# KeepUntil-v2_0.net
KiCad netlist of a schematic drawn in EAGLE
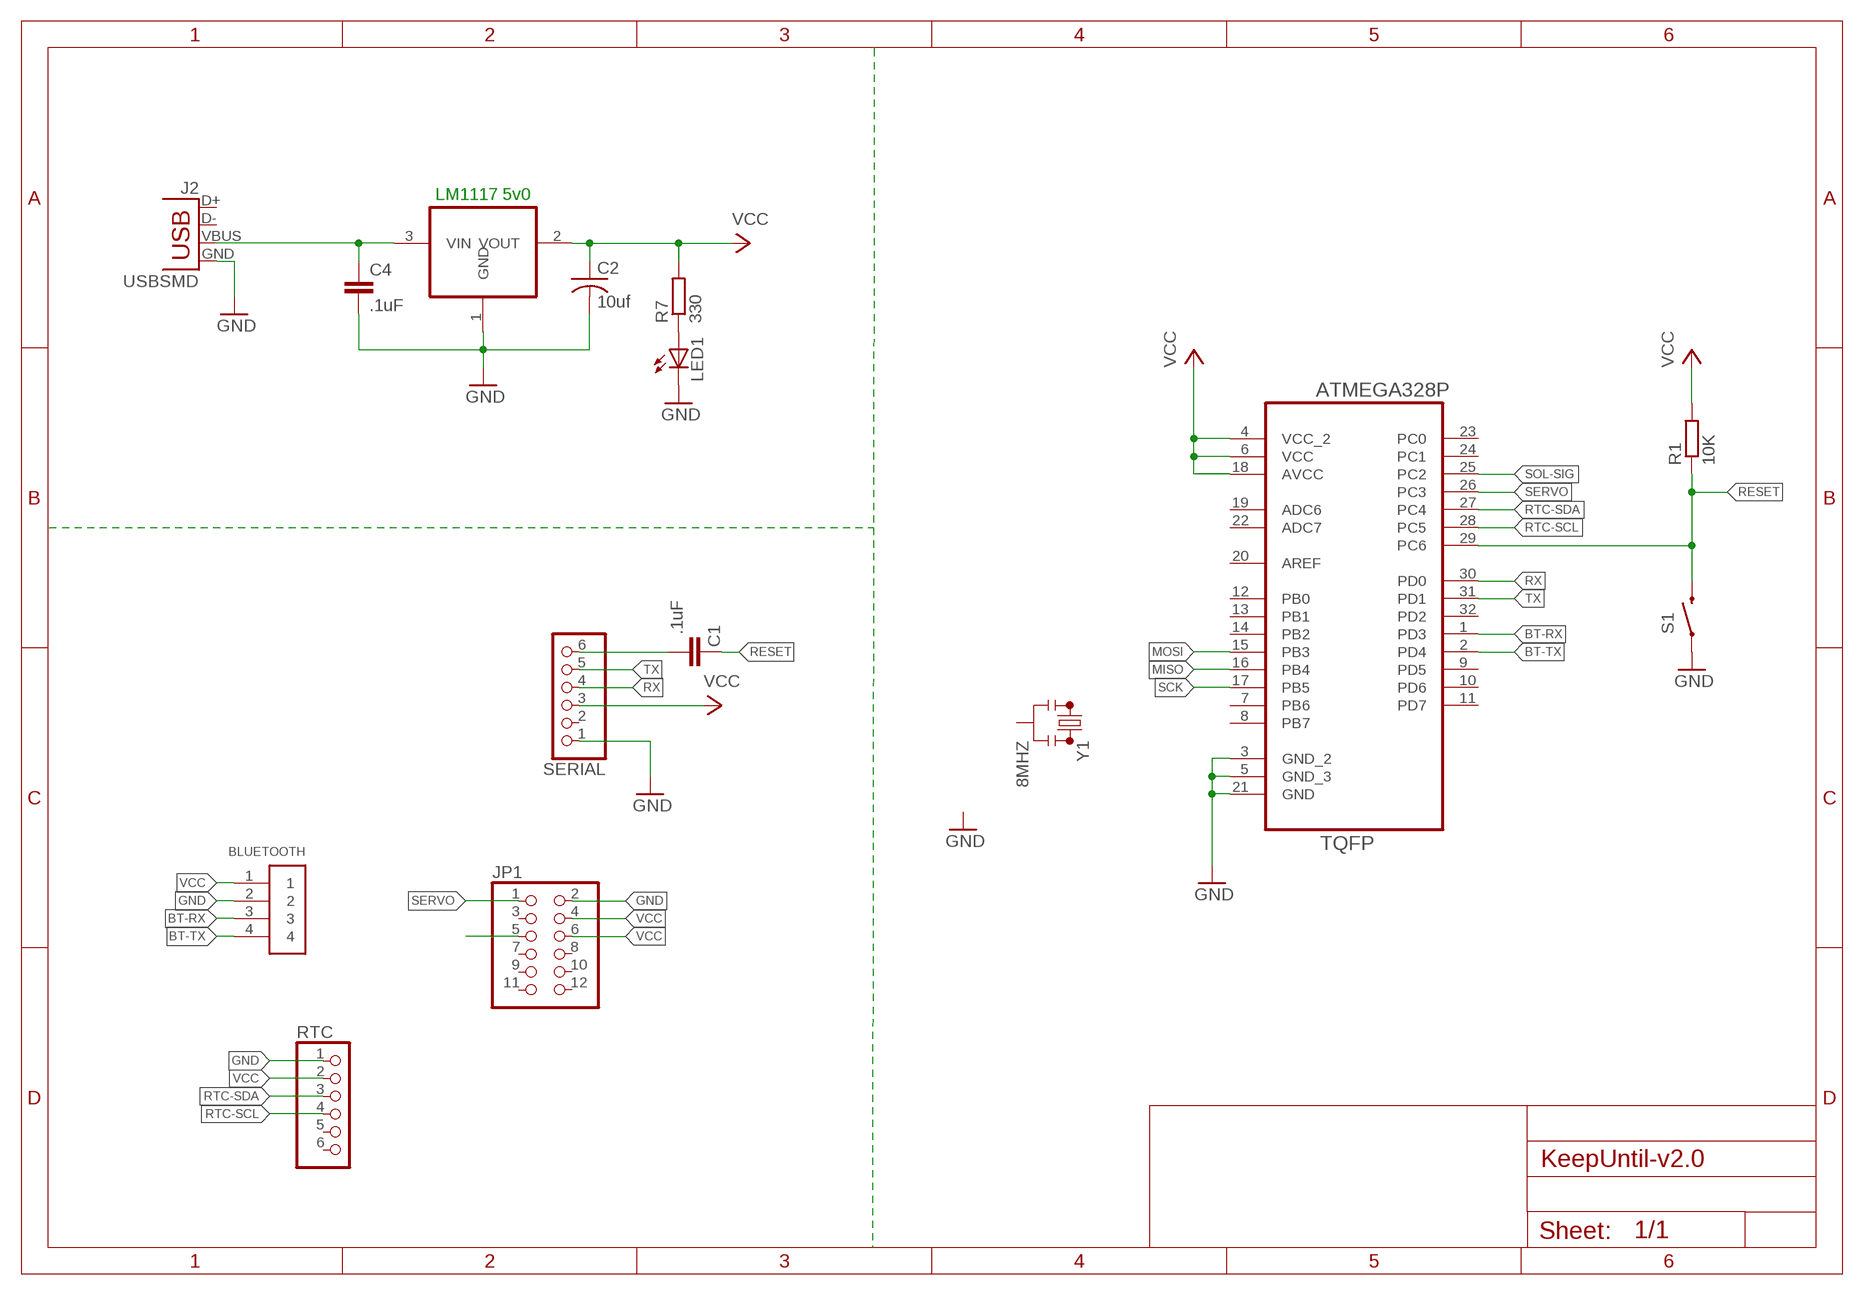
[diagram p0: schematic, sheet 1]

(export (version "E")
  (design (tool "Eeschema 10.0.6"))
  (components
    (comp (ref "BLUETOOTH")
      (value "1X4-CLEANBIG")
      (footprint "eagle-import:1X04-CLEANBIG")
      (libsource (lib "eagle-import") (part "1X4-CLEANBIG"))
    )
    (comp (ref "C1")
      (value ".1uF")
      (footprint "eagle-import:C0805")
      (libsource (lib "eagle-import") (part "C-EUC0805"))
    )
    (comp (ref "C2")
      (value "10uf")
      (footprint "eagle-import:C1206")
      (libsource (lib "eagle-import") (part "C-USC1206"))
    )
    (comp (ref "C4")
      (value ".1uF")
      (footprint "eagle-import:C0805")
      (libsource (lib "eagle-import") (part "C-EUC0805"))
    )
    (comp (ref "IC2")
      (value "REG1117")
      (footprint "eagle-import:SOT223")
      (fields (field (name "MPN") "LM1117 3v3"))
      (libsource (lib "eagle-import") (part "REG1117"))
    )
    (comp (ref "J2")
      (value "USBSMD")
      (footprint "eagle-import:USB-MINIB")
      (libsource (lib "eagle-import") (part "USBSMD"))
    )
    (comp (ref "JP1")
      (value "PINHD-2X6")
      (footprint "eagle-import:2X06")
      (libsource (lib "eagle-import") (part "PINHD-2X6"))
    )
    (comp (ref "LED1")
      (value "LEDSMT1206")
      (footprint "eagle-import:1206")
      (libsource (lib "eagle-import") (part "LEDSMT1206"))
    )
    (comp (ref "R1")
      (value "10K")
      (footprint "eagle-import:R0805")
      (libsource (lib "eagle-import") (part "R-EU_R0805"))
    )
    (comp (ref "R7")
      (value "330")
      (footprint "eagle-import:R0805")
      (libsource (lib "eagle-import") (part "R-EU_R0805"))
    )
    (comp (ref "RTC")
      (value "PINHD-1X6CLEAN")
      (footprint "eagle-import:1X06-CLEAN")
      (libsource (lib "eagle-import") (part "PINHD-1X6CLEAN"))
    )
    (comp (ref "S1")
      (value "SWITCH-MOMENTARY-2SMD-1101NE")
      (footprint "eagle-import:TACTILE-SWITCH-1101NE")
      (libsource (lib "eagle-import") (part "SWITCH-MOMENTARY-2SMD-1101NE"))
    )
    (comp (ref "SERIAL")
      (value "PINHD-1X6CLEAN")
      (footprint "eagle-import:1X06-CLEAN")
      (libsource (lib "eagle-import") (part "PINHD-1X6CLEAN"))
    )
    (comp (ref "U1")
      (value "ATMEGA328P-AU")
      (footprint "eagle-import:QFP80P900X900X120-32N")
      (libsource (lib "eagle-import") (part "ATMEGA328P-AU"))
    )
    (comp (ref "Y1")
      (value "8MHZ")
      (footprint "eagle-import:RESONATOR-SMD")
      (libsource (lib "eagle-import") (part "RESONATOR8MHZ"))
    )
  )
  (nets
    (net (code "1") (name "BT-RX") (class "Default")
      (node (ref "BLUETOOTH") (pin "3") (pinfunction "3_3") (pintype "bidirectional"))
      (node (ref "U1") (pin "1") (pinfunction "PD3_1") (pintype "bidirectional"))
    )
    (net (code "2") (name "BT-TX") (class "Default")
      (node (ref "BLUETOOTH") (pin "4") (pinfunction "4_4") (pintype "bidirectional"))
      (node (ref "U1") (pin "2") (pinfunction "PD4_2") (pintype "bidirectional"))
    )
    (net (code "3") (name "GND") (class "Default")
      (node (ref "BLUETOOTH") (pin "2") (pinfunction "2_2") (pintype "bidirectional"))
      (node (ref "C2") (pin "2") (pinfunction "2_2") (pintype "passive"))
      (node (ref "C4") (pin "2") (pinfunction "2_2") (pintype "passive"))
      (node (ref "IC2") (pin "1") (pinfunction "GND_1") (pintype "power_in"))
      (node (ref "J2") (pin "GND") (pinfunction "GND_GND") (pintype "bidirectional"))
      (node (ref "JP1") (pin "2") (pinfunction "2_2") (pintype "passive"))
      (node (ref "LED1") (pin "C") (pinfunction "C_C") (pintype "passive"))
      (node (ref "RTC") (pin "1") (pinfunction "1_1") (pintype "passive"))
      (node (ref "S1") (pin "1") (pinfunction "1_1") (pintype "passive"))
      (node (ref "SERIAL") (pin "1") (pinfunction "1_1") (pintype "passive"))
      (node (ref "U1") (pin "21") (pinfunction "GND_21") (pintype "passive"))
      (node (ref "U1") (pin "3") (pinfunction "GND_2_3") (pintype "passive"))
      (node (ref "U1") (pin "5") (pinfunction "GND_3_5") (pintype "passive"))
    )
    (net (code "4") (name "MISO") (class "Default")
      (node (ref "U1") (pin "16") (pinfunction "PB4_16") (pintype "bidirectional"))
    )
    (net (code "5") (name "MOSI") (class "Default")
      (node (ref "U1") (pin "15") (pinfunction "PB3_15") (pintype "bidirectional"))
    )
    (net (code "6") (name "Net-(C1-Pad2)") (class "Default")
      (node (ref "C1") (pin "2") (pinfunction "2_2") (pintype "passive"))
      (node (ref "SERIAL") (pin "6") (pinfunction "6_6") (pintype "passive"))
    )
    (net (code "7") (name "Net-(IC2-VIN)") (class "Default")
      (node (ref "C4") (pin "1") (pinfunction "1_1") (pintype "passive"))
      (node (ref "IC2") (pin "3") (pinfunction "VIN_3") (pintype "input"))
      (node (ref "J2") (pin "VBUS") (pinfunction "VBUS_VBUS") (pintype "bidirectional"))
    )
    (net (code "8") (name "Net-(LED1-PadA)") (class "Default")
      (node (ref "LED1") (pin "A") (pinfunction "A_A") (pintype "passive"))
      (node (ref "R7") (pin "1") (pinfunction "1_1") (pintype "passive"))
    )
    (net (code "9") (name "RESET") (class "Default")
      (node (ref "C1") (pin "1") (pinfunction "1_1") (pintype "passive"))
      (node (ref "R1") (pin "1") (pinfunction "1_1") (pintype "passive"))
      (node (ref "S1") (pin "2") (pinfunction "2_2") (pintype "passive"))
      (node (ref "U1") (pin "29") (pinfunction "PC6_29") (pintype "bidirectional"))
    )
    (net (code "10") (name "RTC-SCL") (class "Default")
      (node (ref "RTC") (pin "4") (pinfunction "4_4") (pintype "passive"))
      (node (ref "U1") (pin "28") (pinfunction "PC5_28") (pintype "bidirectional"))
    )
    (net (code "11") (name "RTC-SDA") (class "Default")
      (node (ref "RTC") (pin "3") (pinfunction "3_3") (pintype "passive"))
      (node (ref "U1") (pin "27") (pinfunction "PC4_27") (pintype "bidirectional"))
    )
    (net (code "12") (name "RX") (class "Default")
      (node (ref "SERIAL") (pin "4") (pinfunction "4_4") (pintype "passive"))
      (node (ref "U1") (pin "30") (pinfunction "PD0_30") (pintype "bidirectional"))
    )
    (net (code "13") (name "SCK") (class "Default")
      (node (ref "U1") (pin "17") (pinfunction "PB5_17") (pintype "bidirectional"))
    )
    (net (code "14") (name "SERVO") (class "Default")
      (node (ref "JP1") (pin "1") (pinfunction "1_1") (pintype "passive"))
      (node (ref "U1") (pin "26") (pinfunction "PC3_26") (pintype "bidirectional"))
    )
    (net (code "15") (name "SOL-SIG") (class "Default")
      (node (ref "U1") (pin "25") (pinfunction "PC2_25") (pintype "bidirectional"))
    )
    (net (code "16") (name "TX") (class "Default")
      (node (ref "SERIAL") (pin "5") (pinfunction "5_5") (pintype "passive"))
      (node (ref "U1") (pin "31") (pinfunction "PD1_31") (pintype "bidirectional"))
    )
    (net (code "17") (name "VCC") (class "Default")
      (node (ref "BLUETOOTH") (pin "1") (pinfunction "1_1") (pintype "bidirectional"))
      (node (ref "C2") (pin "1") (pinfunction "1_1") (pintype "passive"))
      (node (ref "IC2") (pin "2") (pinfunction "VOUT_2") (pintype "output"))
      (node (ref "JP1") (pin "4") (pinfunction "4_4") (pintype "passive"))
      (node (ref "JP1") (pin "6") (pinfunction "6_6") (pintype "passive"))
      (node (ref "R1") (pin "2") (pinfunction "2_2") (pintype "passive"))
      (node (ref "R7") (pin "2") (pinfunction "2_2") (pintype "passive"))
      (node (ref "RTC") (pin "2") (pinfunction "2_2") (pintype "passive"))
      (node (ref "SERIAL") (pin "3") (pinfunction "3_3") (pintype "passive"))
      (node (ref "U1") (pin "18") (pinfunction "AVCC_18") (pintype "power_in"))
      (node (ref "U1") (pin "4") (pinfunction "VCC_2_4") (pintype "power_in"))
      (node (ref "U1") (pin "6") (pinfunction "VCC_6") (pintype "power_in"))
    )
    (net (code "18") (name "unconnected-(J2-PadD+)") (class "Default")
      (node (ref "J2") (pin "D+") (pinfunction "D+_D+") (pintype "bidirectional"))
    )
    (net (code "19") (name "unconnected-(J2-PadD-)") (class "Default")
      (node (ref "J2") (pin "D-") (pinfunction "D-_D-") (pintype "bidirectional"))
    )
    (net (code "20") (name "unconnected-(JP1-Pad3)") (class "Default")
      (node (ref "JP1") (pin "3") (pinfunction "3_3") (pintype "passive"))
    )
    (net (code "21") (name "unconnected-(JP1-Pad5)") (class "Default")
      (node (ref "JP1") (pin "5") (pinfunction "5_5") (pintype "passive"))
    )
    (net (code "22") (name "unconnected-(JP1-Pad7)") (class "Default")
      (node (ref "JP1") (pin "7") (pinfunction "7_7") (pintype "passive"))
    )
    (net (code "23") (name "unconnected-(JP1-Pad8)") (class "Default")
      (node (ref "JP1") (pin "8") (pinfunction "8_8") (pintype "passive"))
    )
    (net (code "24") (name "unconnected-(JP1-Pad9)") (class "Default")
      (node (ref "JP1") (pin "9") (pinfunction "9_9") (pintype "passive"))
    )
    (net (code "25") (name "unconnected-(JP1-Pad10)") (class "Default")
      (node (ref "JP1") (pin "10") (pinfunction "10_10") (pintype "passive"))
    )
    (net (code "26") (name "unconnected-(JP1-Pad11)") (class "Default")
      (node (ref "JP1") (pin "11") (pinfunction "11_11") (pintype "passive"))
    )
    (net (code "27") (name "unconnected-(JP1-Pad12)") (class "Default")
      (node (ref "JP1") (pin "12") (pinfunction "12_12") (pintype "passive"))
    )
    (net (code "28") (name "unconnected-(RTC-Pad5)") (class "Default")
      (node (ref "RTC") (pin "5") (pinfunction "5_5") (pintype "passive"))
    )
    (net (code "29") (name "unconnected-(RTC-Pad6)") (class "Default")
      (node (ref "RTC") (pin "6") (pinfunction "6_6") (pintype "passive"))
    )
    (net (code "30") (name "unconnected-(SERIAL-Pad2)") (class "Default")
      (node (ref "SERIAL") (pin "2") (pinfunction "2_2") (pintype "passive"))
    )
    (net (code "31") (name "unconnected-(U1-ADC6-Pad19)") (class "Default")
      (node (ref "U1") (pin "19") (pinfunction "ADC6_19") (pintype "input"))
    )
    (net (code "32") (name "unconnected-(U1-ADC7-Pad22)") (class "Default")
      (node (ref "U1") (pin "22") (pinfunction "ADC7_22") (pintype "input"))
    )
    (net (code "33") (name "unconnected-(U1-AREF-Pad20)") (class "Default")
      (node (ref "U1") (pin "20") (pinfunction "AREF_20") (pintype "input"))
    )
    (net (code "34") (name "unconnected-(U1-PB0-Pad12)") (class "Default")
      (node (ref "U1") (pin "12") (pinfunction "PB0_12") (pintype "bidirectional"))
    )
    (net (code "35") (name "unconnected-(U1-PB1-Pad13)") (class "Default")
      (node (ref "U1") (pin "13") (pinfunction "PB1_13") (pintype "bidirectional"))
    )
    (net (code "36") (name "unconnected-(U1-PB2-Pad14)") (class "Default")
      (node (ref "U1") (pin "14") (pinfunction "PB2_14") (pintype "bidirectional"))
    )
    (net (code "37") (name "unconnected-(U1-PB6-Pad7)") (class "Default")
      (node (ref "U1") (pin "7") (pinfunction "PB6_7") (pintype "bidirectional"))
    )
    (net (code "38") (name "unconnected-(U1-PB7-Pad8)") (class "Default")
      (node (ref "U1") (pin "8") (pinfunction "PB7_8") (pintype "bidirectional"))
    )
    (net (code "39") (name "unconnected-(U1-PC0-Pad23)") (class "Default")
      (node (ref "U1") (pin "23") (pinfunction "PC0_23") (pintype "bidirectional"))
    )
    (net (code "40") (name "unconnected-(U1-PC1-Pad24)") (class "Default")
      (node (ref "U1") (pin "24") (pinfunction "PC1_24") (pintype "bidirectional"))
    )
    (net (code "41") (name "unconnected-(U1-PD2-Pad32)") (class "Default")
      (node (ref "U1") (pin "32") (pinfunction "PD2_32") (pintype "bidirectional"))
    )
    (net (code "42") (name "unconnected-(U1-PD5-Pad9)") (class "Default")
      (node (ref "U1") (pin "9") (pinfunction "PD5_9") (pintype "bidirectional"))
    )
    (net (code "43") (name "unconnected-(U1-PD6-Pad10)") (class "Default")
      (node (ref "U1") (pin "10") (pinfunction "PD6_10") (pintype "bidirectional"))
    )
    (net (code "44") (name "unconnected-(U1-PD7-Pad11)") (class "Default")
      (node (ref "U1") (pin "11") (pinfunction "PD7_11") (pintype "bidirectional"))
    )
    (net (code "45") (name "unconnected-(Y1-Pad1)") (class "Default")
      (node (ref "Y1") (pin "1") (pinfunction "1_1") (pintype "passive"))
    )
    (net (code "46") (name "unconnected-(Y1-Pad2)") (class "Default")
      (node (ref "Y1") (pin "2") (pinfunction "2_2") (pintype "passive"))
    )
    (net (code "47") (name "unconnected-(Y1-Pad3)") (class "Default")
      (node (ref "Y1") (pin "3") (pinfunction "3_3") (pintype "passive"))
    )
  )
)
